# zftplk1.net
KiCad netlist of a schematic drawn in Altium Designer
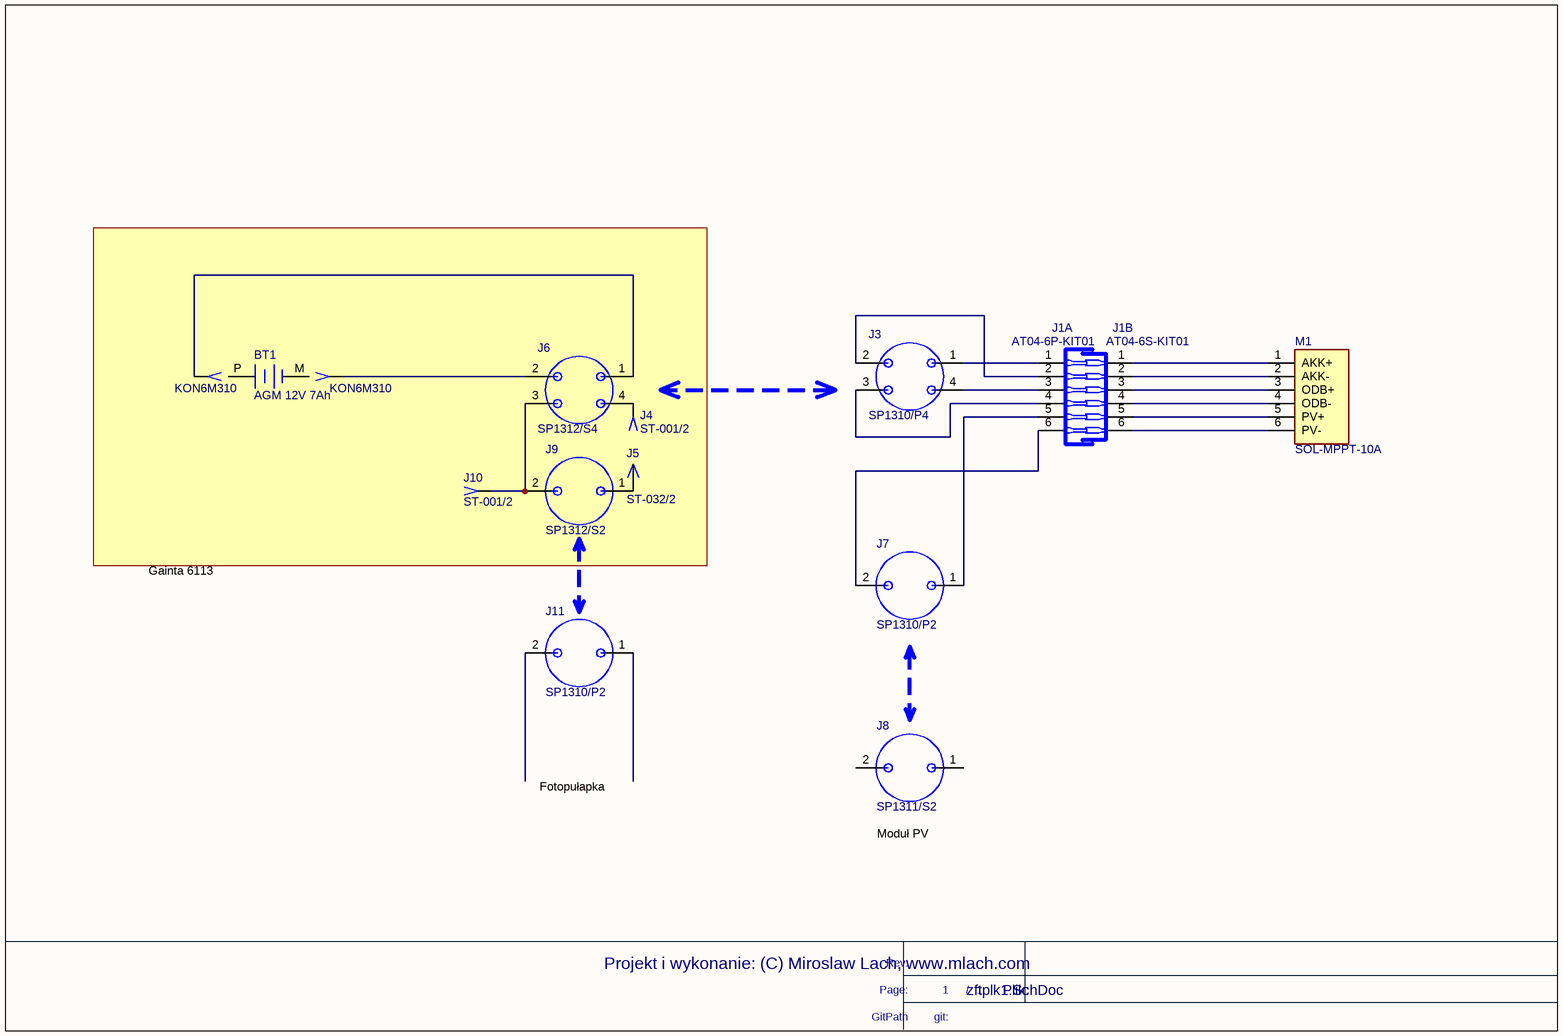
[diagram p0: zftplk1.SchDoc]

(export (version "E")
  (design (tool "Eeschema 10.0.6"))
  (components
    (comp (ref "BT1")
      (value "AGM 12V 7Ah")
      (footprint "-")
      (fields (field (name "MANUFACTURER") "bd"))
      (libsource (lib "PartsMySQL") (part "BATTERY"))
    )
    (comp (ref "J1") (value "KON6M310") (libsource (lib "PartsMySQL") (part "KON6M310")))
    (comp (ref "J1A")
      (value "AT04-6P-KIT01")
      (fields (field (name "MANUFACTURER") "Amphenol"))
      (libsource (lib "PartsMySQL") (part "CONNM6"))
    )
    (comp (ref "J1B")
      (value "AT04-6S-KIT01")
      (fields (field (name "MANUFACTURER") "Amphenol"))
      (libsource (lib "PartsMySQL") (part "CONNF6"))
    )
    (comp (ref "J2") (value "KON6M310") (libsource (lib "PartsMySQL") (part "KON6M310")))
    (comp (ref "J3")
      (value "SP1310/P4")
      (fields (field (name "MANUFACTURER") "WEIPU"))
      (libsource (lib "PartsMySQL") (part "SP1312_S4"))
    )
    (comp (ref "J4")
      (value "ST-001/2")
      (fields (field (name "MANUFACTURER") "Ninigi"))
      (libsource (lib "PartsMySQL") (part "KON6M310F"))
    )
    (comp (ref "J5")
      (value "ST-032/2")
      (fields (field (name "MANUFACTURER") "Ninigi"))
      (libsource (lib "PartsMySQL") (part "KON6M310M"))
    )
    (comp (ref "J6")
      (value "SP1312/S4")
      (fields (field (name "MANUFACTURER") "WEIPU"))
      (libsource (lib "PartsMySQL") (part "SP1312_S4"))
    )
    (comp (ref "J7")
      (value "SP1310/P2")
      (fields (field (name "MANUFACTURER") "WEIPU"))
      (libsource (lib "PartsMySQL") (part "SP13_2PIN"))
    )
    (comp (ref "J8")
      (value "SP1311/S2")
      (fields (field (name "MANUFACTURER") "WEIPU"))
      (libsource (lib "PartsMySQL") (part "SP13_2PIN"))
    )
    (comp (ref "J9")
      (value "SP1312/S2")
      (fields (field (name "MANUFACTURER") "WEIPU"))
      (libsource (lib "PartsMySQL") (part "SP13_2PIN"))
    )
    (comp (ref "J10")
      (value "ST-001/2")
      (fields (field (name "MANUFACTURER") "Ninigi"))
      (libsource (lib "PartsMySQL") (part "KON6M310F"))
    )
    (comp (ref "J11")
      (value "SP1310/P2")
      (fields (field (name "MANUFACTURER") "WEIPU"))
      (libsource (lib "PartsMySQL") (part "SP13_2PIN"))
    )
    (comp (ref "M1")
      (value "SOL-MPPT-10A")
      (footprint "SOL-MPPT-10A")
      (fields (field (name "MANUFACTURER") "Volt Polska"))
      (libsource (lib "PartsMySQL") (part "SOL-MPPT-10A"))
    )
  )
  (nets
    (net (code "1") (name "Net-(J1-Pad1)") (class "Default")
      (node (ref "J1") (pin "1") (pinfunction "1_1") (pintype "passive"))
      (node (ref "J6") (pin "1") (pinfunction "1_1") (pintype "passive"))
    )
    (net (code "2") (name "Net-(J1A-Pad1)") (class "Default")
      (node (ref "J1A") (pin "1") (pinfunction "1_1") (pintype "passive"))
      (node (ref "J3") (pin "1") (pinfunction "1_1") (pintype "passive"))
    )
    (net (code "3") (name "Net-(J1A-Pad2)") (class "Default")
      (node (ref "J1A") (pin "2") (pinfunction "2_2") (pintype "passive"))
      (node (ref "J3") (pin "2") (pinfunction "2_2") (pintype "passive"))
    )
    (net (code "4") (name "Net-(J1A-Pad3)") (class "Default")
      (node (ref "J1A") (pin "3") (pinfunction "3_3") (pintype "passive"))
      (node (ref "J3") (pin "4") (pinfunction "4_4") (pintype "passive"))
    )
    (net (code "5") (name "Net-(J1A-Pad4)") (class "Default")
      (node (ref "J1A") (pin "4") (pinfunction "4_4") (pintype "passive"))
      (node (ref "J3") (pin "3") (pinfunction "3_3") (pintype "passive"))
    )
    (net (code "6") (name "Net-(J1A-Pad5)") (class "Default")
      (node (ref "J1A") (pin "5") (pinfunction "5_5") (pintype "passive"))
      (node (ref "J7") (pin "1") (pinfunction "1_1") (pintype "passive"))
    )
    (net (code "7") (name "Net-(J1A-Pad6)") (class "Default")
      (node (ref "J1A") (pin "6") (pinfunction "6_6") (pintype "passive"))
      (node (ref "J7") (pin "2") (pinfunction "2_2") (pintype "passive"))
    )
    (net (code "8") (name "Net-(J2-Pad1)") (class "Default")
      (node (ref "J2") (pin "1") (pinfunction "1_1") (pintype "passive"))
      (node (ref "J6") (pin "2") (pinfunction "2_2") (pintype "passive"))
    )
    (net (code "9") (name "Net-(J4-Pad1)") (class "Default")
      (node (ref "J4") (pin "1") (pinfunction "1_1") (pintype "passive"))
      (node (ref "J6") (pin "4") (pinfunction "4_4") (pintype "passive"))
    )
    (net (code "10") (name "Net-(J5-Pad1)") (class "Default")
      (node (ref "J5") (pin "1") (pinfunction "1_1") (pintype "passive"))
      (node (ref "J9") (pin "1") (pinfunction "1_1") (pintype "passive"))
    )
    (net (code "11") (name "Net-(J10-Pad1)") (class "Default")
      (node (ref "J10") (pin "1") (pinfunction "1_1") (pintype "passive"))
      (node (ref "J6") (pin "3") (pinfunction "3_3") (pintype "passive"))
      (node (ref "J9") (pin "2") (pinfunction "2_2") (pintype "passive"))
    )
    (net (code "12") (name "Net-(M1-AKK+)") (class "Default")
      (node (ref "J1B") (pin "1") (pinfunction "1_1") (pintype "passive"))
      (node (ref "M1") (pin "1") (pinfunction "AKK+_1") (pintype "passive"))
    )
    (net (code "13") (name "Net-(M1-AKK-)") (class "Default")
      (node (ref "J1B") (pin "2") (pinfunction "2_2") (pintype "passive"))
      (node (ref "M1") (pin "2") (pinfunction "AKK-_2") (pintype "passive"))
    )
    (net (code "14") (name "Net-(M1-ODB+)") (class "Default")
      (node (ref "J1B") (pin "3") (pinfunction "3_3") (pintype "passive"))
      (node (ref "M1") (pin "3") (pinfunction "ODB+_3") (pintype "passive"))
    )
    (net (code "15") (name "Net-(M1-ODB-)") (class "Default")
      (node (ref "J1B") (pin "4") (pinfunction "4_4") (pintype "passive"))
      (node (ref "M1") (pin "4") (pinfunction "ODB-_4") (pintype "passive"))
    )
    (net (code "16") (name "Net-(M1-PV+)") (class "Default")
      (node (ref "J1B") (pin "5") (pinfunction "5_5") (pintype "passive"))
      (node (ref "M1") (pin "5") (pinfunction "PV+_5") (pintype "passive"))
    )
    (net (code "17") (name "Net-(M1-PV-)") (class "Default")
      (node (ref "J1B") (pin "6") (pinfunction "6_6") (pintype "passive"))
      (node (ref "M1") (pin "6") (pinfunction "PV-_6") (pintype "passive"))
    )
    (net (code "18") (name "unconnected-(BT1-MINU-PadM)") (class "Default")
      (node (ref "BT1") (pin "M") (pinfunction "MINU_M") (pintype "passive"))
    )
    (net (code "19") (name "unconnected-(BT1-PLUS-PadP)") (class "Default")
      (node (ref "BT1") (pin "P") (pinfunction "PLUS_P") (pintype "passive"))
    )
    (net (code "20") (name "unconnected-(J8-Pad1)") (class "Default")
      (node (ref "J8") (pin "1") (pinfunction "1_1") (pintype "passive"))
    )
    (net (code "21") (name "unconnected-(J8-Pad2)") (class "Default")
      (node (ref "J8") (pin "2") (pinfunction "2_2") (pintype "passive"))
    )
    (net (code "22") (name "unconnected-(J11-Pad1)") (class "Default")
      (node (ref "J11") (pin "1") (pinfunction "1_1") (pintype "passive"))
    )
    (net (code "23") (name "unconnected-(J11-Pad2)") (class "Default")
      (node (ref "J11") (pin "2") (pinfunction "2_2") (pintype "passive"))
    )
  )
)
